# TIA_Schematic_19_Jan_2017.net
KiCad netlist of a schematic drawn in EAGLE
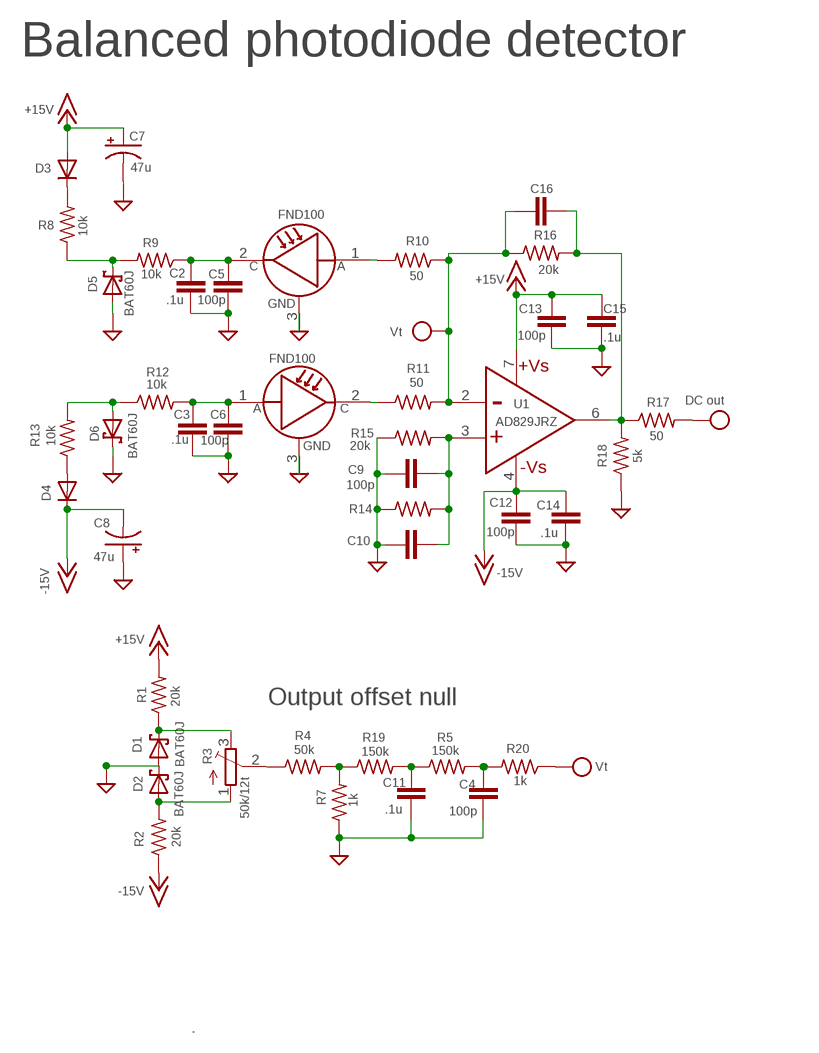
[diagram p0: schematic, sheet 1]

(export (version "E")
  (design (tool "Eeschema 10.0.6"))
  (components
    (comp (ref "C2")
      (value ".1u")
      (footprint "eagle-import:C0603")
      (libsource (lib "eagle-import") (part "C-EUC0603"))
    )
    (comp (ref "C3")
      (value ".1u")
      (footprint "eagle-import:C0603")
      (libsource (lib "eagle-import") (part "C-EUC0603"))
    )
    (comp (ref "C4")
      (value "100p")
      (footprint "eagle-import:C0603")
      (libsource (lib "eagle-import") (part "C-EUC0603"))
    )
    (comp (ref "C5")
      (value "100p")
      (footprint "eagle-import:C0603")
      (libsource (lib "eagle-import") (part "C-EUC0603"))
    )
    (comp (ref "C6")
      (value "100p")
      (footprint "eagle-import:C0603")
      (libsource (lib "eagle-import") (part "C-EUC0603"))
    )
    (comp (ref "C7")
      (value "47u")
      (footprint "eagle-import:ETR3")
      (libsource (lib "eagle-import") (part "CPOL-USETR3"))
    )
    (comp (ref "C8")
      (value "47u")
      (footprint "eagle-import:ETR3")
      (libsource (lib "eagle-import") (part "CPOL-USETR3"))
    )
    (comp (ref "C9")
      (value "100p")
      (footprint "eagle-import:C0603")
      (libsource (lib "eagle-import") (part "C-EUC0603"))
    )
    (comp (ref "C10")
      (value "C-EUC0603")
      (footprint "eagle-import:C0603")
      (libsource (lib "eagle-import") (part "C-EUC0603"))
    )
    (comp (ref "C11")
      (value ".1u")
      (footprint "eagle-import:C0603")
      (libsource (lib "eagle-import") (part "C-EUC0603"))
    )
    (comp (ref "C12")
      (value "100p")
      (footprint "eagle-import:C0603")
      (libsource (lib "eagle-import") (part "C-EUC0603"))
    )
    (comp (ref "C13")
      (value "100p")
      (footprint "eagle-import:C0603")
      (libsource (lib "eagle-import") (part "C-EUC0603"))
    )
    (comp (ref "C14")
      (value ".1u")
      (footprint "eagle-import:C0603")
      (libsource (lib "eagle-import") (part "C-EUC0603"))
    )
    (comp (ref "C15")
      (value ".1u")
      (footprint "eagle-import:C0603")
      (libsource (lib "eagle-import") (part "C-EUC0603"))
    )
    (comp (ref "C16")
      (value "C-EUC0603")
      (footprint "eagle-import:C0603")
      (libsource (lib "eagle-import") (part "C-EUC0603"))
    )
    (comp (ref "D1")
      (value "BAT60J")
      (footprint "eagle-import:SOD323_ST")
      (libsource (lib "eagle-import") (part "BAT60J"))
    )
    (comp (ref "D2")
      (value "BAT60J")
      (footprint "eagle-import:SOD323_ST")
      (libsource (lib "eagle-import") (part "BAT60J"))
    )
    (comp (ref "D3")
      (value "SOD523DIODE")
      (footprint "eagle-import:SOD523")
      (libsource (lib "eagle-import") (part "SOD523DIODE"))
    )
    (comp (ref "D4")
      (value "SOD523DIODE")
      (footprint "eagle-import:SOD523")
      (libsource (lib "eagle-import") (part "SOD523DIODE"))
    )
    (comp (ref "D5")
      (value "BAT60J")
      (footprint "eagle-import:SOD323_ST")
      (libsource (lib "eagle-import") (part "BAT60J"))
    )
    (comp (ref "D6")
      (value "BAT60J")
      (footprint "eagle-import:SOD323_ST")
      (libsource (lib "eagle-import") (part "BAT60J"))
    )
    (comp (ref "R1")
      (value "20k")
      (footprint "eagle-import:R0603")
      (libsource (lib "eagle-import") (part "R-US_R0603"))
    )
    (comp (ref "R2")
      (value "20k")
      (footprint "eagle-import:R0603")
      (libsource (lib "eagle-import") (part "R-US_R0603"))
    )
    (comp (ref "R3")
      (value "50k/12t")
      (footprint "eagle-import:3223G")
      (libsource (lib "eagle-import") (part "TRIM_EU-3223G"))
    )
    (comp (ref "R4")
      (value "50k")
      (footprint "eagle-import:R0603")
      (libsource (lib "eagle-import") (part "R-US_R0603"))
    )
    (comp (ref "R5")
      (value "150k")
      (footprint "eagle-import:R0603")
      (libsource (lib "eagle-import") (part "R-US_R0603"))
    )
    (comp (ref "R7")
      (value "1k")
      (footprint "eagle-import:R0603")
      (libsource (lib "eagle-import") (part "R-US_R0603"))
    )
    (comp (ref "R8")
      (value "10k")
      (footprint "eagle-import:R0603")
      (libsource (lib "eagle-import") (part "R-US_R0603"))
    )
    (comp (ref "R9")
      (value "10k")
      (footprint "eagle-import:R0603")
      (libsource (lib "eagle-import") (part "R-US_R0603"))
    )
    (comp (ref "R10")
      (value "50")
      (footprint "eagle-import:R0603")
      (libsource (lib "eagle-import") (part "R-US_R0603"))
    )
    (comp (ref "R11")
      (value "50")
      (footprint "eagle-import:R0603")
      (libsource (lib "eagle-import") (part "R-US_R0603"))
    )
    (comp (ref "R12")
      (value "10k")
      (footprint "eagle-import:R0603")
      (libsource (lib "eagle-import") (part "R-US_R0603"))
    )
    (comp (ref "R13")
      (value "10k")
      (footprint "eagle-import:R0603")
      (libsource (lib "eagle-import") (part "R-US_R0603"))
    )
    (comp (ref "R14")
      (value "R-US_R0603")
      (footprint "eagle-import:R0603")
      (libsource (lib "eagle-import") (part "R-US_R0603"))
    )
    (comp (ref "R15")
      (value "20k")
      (footprint "eagle-import:R0603")
      (libsource (lib "eagle-import") (part "R-US_R0603"))
    )
    (comp (ref "R16")
      (value "20k")
      (footprint "eagle-import:R0603")
      (libsource (lib "eagle-import") (part "R-US_R0603"))
    )
    (comp (ref "R17")
      (value "50")
      (footprint "eagle-import:R0603")
      (libsource (lib "eagle-import") (part "R-US_R0603"))
    )
    (comp (ref "R18")
      (value "5k")
      (footprint "eagle-import:R0603")
      (libsource (lib "eagle-import") (part "R-US_R0603"))
    )
    (comp (ref "R19")
      (value "150k")
      (footprint "eagle-import:R0603")
      (libsource (lib "eagle-import") (part "R-US_R0603"))
    )
    (comp (ref "R20")
      (value "1k")
      (footprint "eagle-import:R0603")
      (libsource (lib "eagle-import") (part "R-US_R0603"))
    )
    (comp (ref "U$1")
      (value "FND100")
      (footprint "eagle-import:TO254P939X470-3P")
      (libsource (lib "eagle-import") (part "FND100"))
    )
    (comp (ref "U$2")
      (value "FND100")
      (footprint "eagle-import:TO254P939X470-3P")
      (libsource (lib "eagle-import") (part "FND100"))
    )
    (comp (ref "U1")
      (value "AD829JRZ")
      (footprint "eagle-import:SOIC127P600X175-8N")
      (libsource (lib "eagle-import") (part "AD829JRZ"))
    )
  )
  (nets
    (net (code "1") (name "+15V") (class "Default")
      (node (ref "C13") (pin "2") (pinfunction "2_2") (pintype "passive"))
      (node (ref "C15") (pin "2") (pinfunction "2_2") (pintype "passive"))
      (node (ref "C7") (pin "+") (pinfunction "+_+") (pintype "passive"))
      (node (ref "D3") (pin "A") (pinfunction "A_A") (pintype "passive"))
      (node (ref "R1") (pin "2") (pinfunction "2_2") (pintype "passive"))
      (node (ref "U1") (pin "7") (pinfunction "+VS_7") (pintype "power_in"))
    )
    (net (code "2") (name "-15V") (class "Default")
      (node (ref "C12") (pin "2") (pinfunction "2_2") (pintype "passive"))
      (node (ref "C14") (pin "2") (pinfunction "2_2") (pintype "passive"))
      (node (ref "C8") (pin "-") (pinfunction "-_-") (pintype "passive"))
      (node (ref "D4") (pin "C") (pinfunction "C_C") (pintype "passive"))
      (node (ref "R2") (pin "1") (pinfunction "1_1") (pintype "passive"))
      (node (ref "U1") (pin "4") (pinfunction "-VS_4") (pintype "power_in"))
    )
    (net (code "3") (name "GND") (class "Default")
      (node (ref "C10") (pin "1") (pinfunction "1_1") (pintype "passive"))
      (node (ref "C11") (pin "1") (pinfunction "1_1") (pintype "passive"))
      (node (ref "C12") (pin "1") (pinfunction "1_1") (pintype "passive"))
      (node (ref "C13") (pin "1") (pinfunction "1_1") (pintype "passive"))
      (node (ref "C14") (pin "1") (pinfunction "1_1") (pintype "passive"))
      (node (ref "C15") (pin "1") (pinfunction "1_1") (pintype "passive"))
      (node (ref "C2") (pin "1") (pinfunction "1_1") (pintype "passive"))
      (node (ref "C3") (pin "1") (pinfunction "1_1") (pintype "passive"))
      (node (ref "C4") (pin "1") (pinfunction "1_1") (pintype "passive"))
      (node (ref "C5") (pin "1") (pinfunction "1_1") (pintype "passive"))
      (node (ref "C6") (pin "1") (pinfunction "1_1") (pintype "passive"))
      (node (ref "C7") (pin "-") (pinfunction "-_-") (pintype "passive"))
      (node (ref "C8") (pin "+") (pinfunction "+_+") (pintype "passive"))
      (node (ref "C9") (pin "1") (pinfunction "1_1") (pintype "passive"))
      (node (ref "D1") (pin "A") (pinfunction "A_A") (pintype "passive"))
      (node (ref "D2") (pin "C") (pinfunction "C_C") (pintype "passive"))
      (node (ref "D5") (pin "A") (pinfunction "A_A") (pintype "passive"))
      (node (ref "D6") (pin "C") (pinfunction "C_C") (pintype "passive"))
      (node (ref "R14") (pin "1") (pinfunction "1_1") (pintype "passive"))
      (node (ref "R15") (pin "1") (pinfunction "1_1") (pintype "passive"))
      (node (ref "R18") (pin "1") (pinfunction "1_1") (pintype "passive"))
      (node (ref "R7") (pin "1") (pinfunction "1_1") (pintype "passive"))
      (node (ref "U$1") (pin "3") (pinfunction "GND_3") (pintype "bidirectional"))
      (node (ref "U$2") (pin "3") (pinfunction "GND_3") (pintype "bidirectional"))
    )
    (net (code "4") (name "Net-(C4-Pad2)") (class "Default")
      (node (ref "C4") (pin "2") (pinfunction "2_2") (pintype "passive"))
      (node (ref "R20") (pin "2") (pinfunction "2_2") (pintype "passive"))
      (node (ref "R5") (pin "2") (pinfunction "2_2") (pintype "passive"))
    )
    (net (code "5") (name "Net-(C11-Pad2)") (class "Default")
      (node (ref "C11") (pin "2") (pinfunction "2_2") (pintype "passive"))
      (node (ref "R19") (pin "2") (pinfunction "2_2") (pintype "passive"))
      (node (ref "R5") (pin "1") (pinfunction "1_1") (pintype "passive"))
    )
    (net (code "6") (name "Net-(D3-PadC)") (class "Default")
      (node (ref "D3") (pin "C") (pinfunction "C_C") (pintype "passive"))
      (node (ref "R8") (pin "2") (pinfunction "2_2") (pintype "passive"))
    )
    (net (code "7") (name "Net-(D4-PadA)") (class "Default")
      (node (ref "D4") (pin "A") (pinfunction "A_A") (pintype "passive"))
      (node (ref "R13") (pin "1") (pinfunction "1_1") (pintype "passive"))
    )
    (net (code "8") (name "Net-(D5-PadC)") (class "Default")
      (node (ref "D5") (pin "C") (pinfunction "C_C") (pintype "passive"))
      (node (ref "R8") (pin "1") (pinfunction "1_1") (pintype "passive"))
      (node (ref "R9") (pin "2") (pinfunction "2_2") (pintype "passive"))
    )
    (net (code "9") (name "Net-(D6-PadA)") (class "Default")
      (node (ref "D6") (pin "A") (pinfunction "A_A") (pintype "passive"))
      (node (ref "R12") (pin "1") (pinfunction "1_1") (pintype "passive"))
      (node (ref "R13") (pin "2") (pinfunction "2_2") (pintype "passive"))
    )
    (net (code "10") (name "Net-(R3-A)") (class "Default")
      (node (ref "D2") (pin "A") (pinfunction "A_A") (pintype "passive"))
      (node (ref "R2") (pin "2") (pinfunction "2_2") (pintype "passive"))
      (node (ref "R3") (pin "1") (pinfunction "A_1") (pintype "passive"))
    )
    (net (code "11") (name "Net-(R3-E)") (class "Default")
      (node (ref "D1") (pin "C") (pinfunction "C_C") (pintype "passive"))
      (node (ref "R1") (pin "1") (pinfunction "1_1") (pintype "passive"))
      (node (ref "R3") (pin "3") (pinfunction "E_3") (pintype "passive"))
    )
    (net (code "12") (name "Net-(R3-S)") (class "Default")
      (node (ref "R3") (pin "2") (pinfunction "S_2") (pintype "passive"))
      (node (ref "R4") (pin "1") (pinfunction "1_1") (pintype "passive"))
    )
    (net (code "13") (name "Net-(R19-Pad1)") (class "Default")
      (node (ref "R19") (pin "1") (pinfunction "1_1") (pintype "passive"))
      (node (ref "R4") (pin "2") (pinfunction "2_2") (pintype "passive"))
      (node (ref "R7") (pin "2") (pinfunction "2_2") (pintype "passive"))
    )
    (net (code "14") (name "Net-(U$1-A)") (class "Default")
      (node (ref "R10") (pin "2") (pinfunction "2_2") (pintype "passive"))
      (node (ref "U$1") (pin "1") (pinfunction "A_1") (pintype "bidirectional"))
    )
    (net (code "15") (name "Net-(U$1-C)") (class "Default")
      (node (ref "C2") (pin "2") (pinfunction "2_2") (pintype "passive"))
      (node (ref "C5") (pin "2") (pinfunction "2_2") (pintype "passive"))
      (node (ref "R9") (pin "1") (pinfunction "1_1") (pintype "passive"))
      (node (ref "U$1") (pin "2") (pinfunction "C_2") (pintype "bidirectional"))
    )
    (net (code "16") (name "Net-(U$2-A)") (class "Default")
      (node (ref "C3") (pin "2") (pinfunction "2_2") (pintype "passive"))
      (node (ref "C6") (pin "2") (pinfunction "2_2") (pintype "passive"))
      (node (ref "R12") (pin "2") (pinfunction "2_2") (pintype "passive"))
      (node (ref "U$2") (pin "1") (pinfunction "A_1") (pintype "bidirectional"))
    )
    (net (code "17") (name "Net-(U$2-C)") (class "Default")
      (node (ref "R11") (pin "1") (pinfunction "1_1") (pintype "passive"))
      (node (ref "U$2") (pin "2") (pinfunction "C_2") (pintype "bidirectional"))
    )
    (net (code "18") (name "Net-(U1-+IN)") (class "Default")
      (node (ref "C10") (pin "2") (pinfunction "2_2") (pintype "passive"))
      (node (ref "C9") (pin "2") (pinfunction "2_2") (pintype "passive"))
      (node (ref "R14") (pin "2") (pinfunction "2_2") (pintype "passive"))
      (node (ref "R15") (pin "2") (pinfunction "2_2") (pintype "passive"))
      (node (ref "U1") (pin "3") (pinfunction "+IN_3") (pintype "input"))
    )
    (net (code "19") (name "Net-(U1-OUTPUT)") (class "Default")
      (node (ref "C16") (pin "2") (pinfunction "2_2") (pintype "passive"))
      (node (ref "R16") (pin "2") (pinfunction "2_2") (pintype "passive"))
      (node (ref "R17") (pin "1") (pinfunction "1_1") (pintype "passive"))
      (node (ref "R18") (pin "2") (pinfunction "2_2") (pintype "passive"))
      (node (ref "U1") (pin "6") (pinfunction "OUTPUT_6") (pintype "output"))
    )
    (net (code "20") (name "VPP") (class "Default")
      (node (ref "C16") (pin "1") (pinfunction "1_1") (pintype "passive"))
      (node (ref "R10") (pin "1") (pinfunction "1_1") (pintype "passive"))
      (node (ref "R11") (pin "2") (pinfunction "2_2") (pintype "passive"))
      (node (ref "R16") (pin "1") (pinfunction "1_1") (pintype "passive"))
      (node (ref "R20") (pin "1") (pinfunction "1_1") (pintype "passive"))
      (node (ref "U1") (pin "2") (pinfunction "-IN_2") (pintype "input"))
    )
    (net (code "21") (name "VSS") (class "Default")
      (node (ref "R17") (pin "2") (pinfunction "2_2") (pintype "passive"))
    )
  )
)
